# Bipolar_Offset_Shifter.net
KiCad netlist of a schematic drawn in Altium Designer
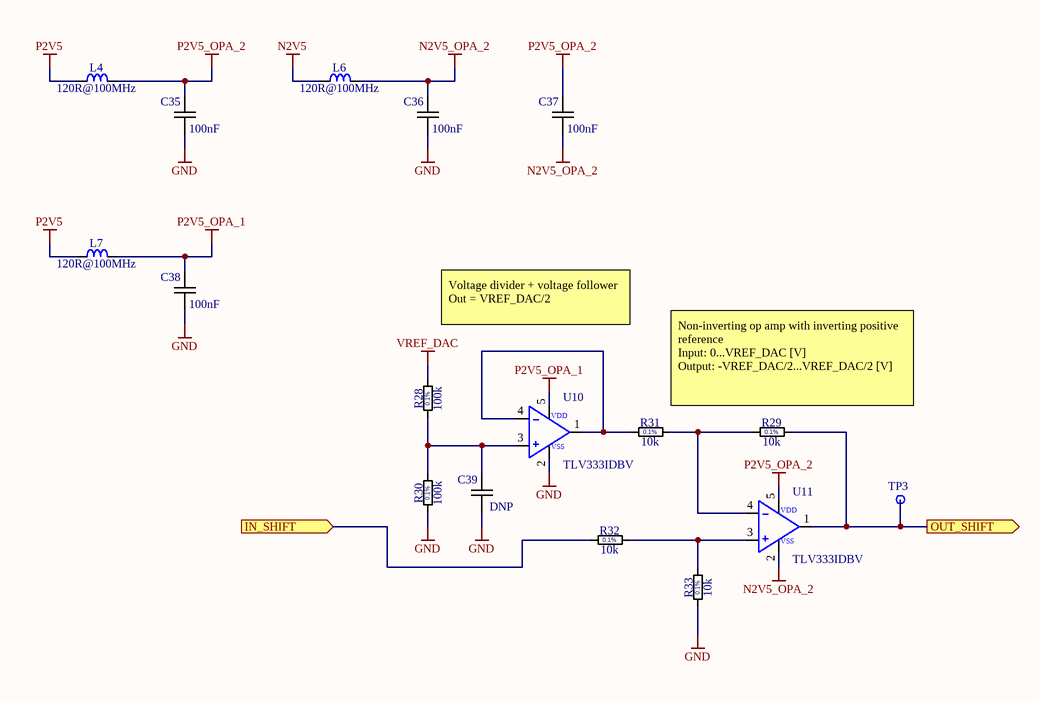
[diagram p0: Bipolar_Offset_Shifter.SchDoc]

(export (version "E")
  (design (tool "Eeschema 10.0.6"))
  (components
    (comp (ref "C35")
      (value "100nF")
      (footprint "CAPC0603X90N")
      (description "Non-polarised capacitor")
      (fields (field (name "MANUFACTURER PART NUMBER") "VJ0603Y104KXJCW1BC"))
      (libsource (lib "Capacitors") (part "Capacitor - non polarized"))
    )
    (comp (ref "C36")
      (value "100nF")
      (footprint "CAPC0603X90N")
      (description "Non-polarised capacitor")
      (fields (field (name "MANUFACTURER PART NUMBER") "VJ0603Y104KXJCW1BC"))
      (libsource (lib "Capacitors") (part "Capacitor - non polarized"))
    )
    (comp (ref "C37")
      (value "100nF")
      (footprint "CAPC0603X90N")
      (description "Non-polarised capacitor")
      (fields (field (name "MANUFACTURER PART NUMBER") "VJ0603Y104KXJCW1BC"))
      (libsource (lib "Capacitors") (part "Capacitor - non polarized"))
    )
    (comp (ref "C38")
      (value "100nF")
      (footprint "CAPC0603X90N")
      (description "Non-polarised capacitor")
      (fields (field (name "MANUFACTURER PART NUMBER") "VJ0603Y104KXJCW1BC"))
      (libsource (lib "Capacitors") (part "Capacitor - non polarized"))
    )
    (comp (ref "C39")
      (value "DNP")
      (footprint "CAPC0603X90N")
      (description "Non-polarised capacitor")
      (fields (field (name "MANUFACTURER PART NUMBER") "UNDEFINED"))
      (libsource (lib "Capacitors") (part "Capacitor - non polarized"))
    )
    (comp (ref "L4")
      (value "120R@100MHz")
      (footprint "INDC0603X90N")
      (description "Ferrite Bead")
      (fields (field (name "MANUFACTURER PART NUMBER") "BLM18PG121SN1D") (field (name "TOLERANCE") "25%"))
      (libsource (lib "Inductors") (part "Inductor"))
    )
    (comp (ref "L6")
      (value "120R@100MHz")
      (footprint "INDC0603X90N")
      (description "Ferrite Bead")
      (fields (field (name "MANUFACTURER PART NUMBER") "BLM18PG121SN1D") (field (name "TOLERANCE") "25%"))
      (libsource (lib "Inductors") (part "Inductor"))
    )
    (comp (ref "L7")
      (value "120R@100MHz")
      (footprint "INDC0603X90N")
      (description "Ferrite Bead")
      (fields (field (name "MANUFACTURER PART NUMBER") "BLM18PG121SN1D") (field (name "TOLERANCE") "25%"))
      (libsource (lib "Inductors") (part "Inductor"))
    )
    (comp (ref "R28")
      (value "100k")
      (footprint "RESC0603X60N")
      (description "General Purpose Thick Film Chip Resistor")
      (fields (field (name "MANUFACTURER PART NUMBER") "RT0603BRD07100KL") (field (name "TOLERANCE") "0.10%"))
      (libsource (lib "Resistors") (part "Resistor - 0.1%"))
    )
    (comp (ref "R29")
      (value "10k")
      (footprint "RESC0603X60N")
      (description "General Purpose Thick Film Chip Resistor")
      (fields (field (name "MANUFACTURER PART NUMBER") "RT0603BRD0710KL") (field (name "TOLERANCE") "0.10%"))
      (libsource (lib "Resistors") (part "Resistor - 0.1%"))
    )
    (comp (ref "R30")
      (value "100k")
      (footprint "RESC0603X60N")
      (description "General Purpose Thick Film Chip Resistor")
      (fields (field (name "MANUFACTURER PART NUMBER") "RT0603BRD07100KL") (field (name "TOLERANCE") "0.10%"))
      (libsource (lib "Resistors") (part "Resistor - 0.1%"))
    )
    (comp (ref "R31")
      (value "10k")
      (footprint "RESC0603X60N")
      (description "General Purpose Thick Film Chip Resistor")
      (fields (field (name "MANUFACTURER PART NUMBER") "RT0603BRD0710KL") (field (name "TOLERANCE") "0.10%"))
      (libsource (lib "Resistors") (part "Resistor - 0.1%"))
    )
    (comp (ref "R32")
      (value "10k")
      (footprint "RESC0603X60N")
      (description "General Purpose Thick Film Chip Resistor")
      (fields (field (name "MANUFACTURER PART NUMBER") "RT0603BRD0710KL") (field (name "TOLERANCE") "0.10%"))
      (libsource (lib "Resistors") (part "Resistor - 0.1%"))
    )
    (comp (ref "R33")
      (value "10k")
      (footprint "RESC0603X60N")
      (description "General Purpose Thick Film Chip Resistor")
      (fields (field (name "MANUFACTURER PART NUMBER") "RT0603BRD0710KL") (field (name "TOLERANCE") "0.10%"))
      (libsource (lib "Resistors") (part "Resistor - 0.1%"))
    )
    (comp (ref "TP3")
      (value "TestPoint")
      (footprint "TESTPOINT_SMD_C1P27MM")
      (description "1.27mm diameter SMD Test Point Area")
      (libsource (lib "Mechanical_and_PCB_Features") (part "Test Point"))
    )
    (comp (ref "U10")
      (value "TLV333IDBV")
      (footprint "SOT23-5")
      (libsource (lib "ICs_and_Semiconductors") (part "TLV333IDBV"))
    )
    (comp (ref "U11")
      (value "TLV333IDBV")
      (footprint "SOT23-5")
      (libsource (lib "ICs_and_Semiconductors") (part "TLV333IDBV"))
    )
  )
  (nets
    (net (code "1") (name "/IN_SHIFT") (class "Default")
      (node (ref "R32") (pin "1") (pinfunction "1_1") (pintype "passive"))
    )
    (net (code "2") (name "/OUT_SHIFT") (class "Default")
      (node (ref "R29") (pin "2") (pinfunction "2_2") (pintype "passive"))
      (node (ref "TP3") (pin "1") (pinfunction "1_1") (pintype "bidirectional"))
      (node (ref "U11") (pin "1") (pinfunction "1_1") (pintype "passive"))
    )
    (net (code "3") (name "GND") (class "Default")
      (node (ref "C35") (pin "2") (pinfunction "2_2") (pintype "passive"))
      (node (ref "C36") (pin "2") (pinfunction "2_2") (pintype "passive"))
      (node (ref "C38") (pin "2") (pinfunction "2_2") (pintype "passive"))
      (node (ref "C39") (pin "2") (pinfunction "2_2") (pintype "passive"))
      (node (ref "R30") (pin "1") (pinfunction "1_1") (pintype "passive"))
      (node (ref "R33") (pin "1") (pinfunction "1_1") (pintype "passive"))
      (node (ref "U10") (pin "2") (pinfunction "VSS_2") (pintype "power_in"))
    )
    (net (code "4") (name "N2V5") (class "Default")
      (node (ref "L6") (pin "1") (pinfunction "1_1") (pintype "passive"))
    )
    (net (code "5") (name "N2V5_OPA_2") (class "Default")
      (node (ref "C36") (pin "1") (pinfunction "1_1") (pintype "passive"))
      (node (ref "C37") (pin "2") (pinfunction "2_2") (pintype "passive"))
      (node (ref "L6") (pin "2") (pinfunction "2_2") (pintype "passive"))
      (node (ref "U11") (pin "2") (pinfunction "VSS_2") (pintype "power_in"))
    )
    (net (code "6") (name "Net-(C39-Pad1)") (class "Default")
      (node (ref "C39") (pin "1") (pinfunction "1_1") (pintype "passive"))
      (node (ref "R28") (pin "1") (pinfunction "1_1") (pintype "passive"))
      (node (ref "R30") (pin "2") (pinfunction "2_2") (pintype "passive"))
      (node (ref "U10") (pin "3") (pinfunction "3_3") (pintype "passive"))
    )
    (net (code "7") (name "Net-(R29-Pad1)") (class "Default")
      (node (ref "R29") (pin "1") (pinfunction "1_1") (pintype "passive"))
      (node (ref "R31") (pin "2") (pinfunction "2_2") (pintype "passive"))
      (node (ref "U11") (pin "4") (pinfunction "4_4") (pintype "passive"))
    )
    (net (code "8") (name "Net-(R31-Pad1)") (class "Default")
      (node (ref "R31") (pin "1") (pinfunction "1_1") (pintype "passive"))
      (node (ref "U10") (pin "1") (pinfunction "1_1") (pintype "passive"))
      (node (ref "U10") (pin "4") (pinfunction "4_4") (pintype "passive"))
    )
    (net (code "9") (name "Net-(R32-Pad2)") (class "Default")
      (node (ref "R32") (pin "2") (pinfunction "2_2") (pintype "passive"))
      (node (ref "R33") (pin "2") (pinfunction "2_2") (pintype "passive"))
      (node (ref "U11") (pin "3") (pinfunction "3_3") (pintype "passive"))
    )
    (net (code "10") (name "P2V5") (class "Default")
      (node (ref "L4") (pin "1") (pinfunction "1_1") (pintype "passive"))
      (node (ref "L7") (pin "1") (pinfunction "1_1") (pintype "passive"))
    )
    (net (code "11") (name "P2V5_OPA_1") (class "Default")
      (node (ref "C38") (pin "1") (pinfunction "1_1") (pintype "passive"))
      (node (ref "L7") (pin "2") (pinfunction "2_2") (pintype "passive"))
      (node (ref "U10") (pin "5") (pinfunction "VDD_5") (pintype "power_in"))
    )
    (net (code "12") (name "P2V5_OPA_2") (class "Default")
      (node (ref "C35") (pin "1") (pinfunction "1_1") (pintype "passive"))
      (node (ref "C37") (pin "1") (pinfunction "1_1") (pintype "passive"))
      (node (ref "L4") (pin "2") (pinfunction "2_2") (pintype "passive"))
      (node (ref "U11") (pin "5") (pinfunction "VDD_5") (pintype "power_in"))
    )
    (net (code "13") (name "VREF_DAC") (class "Default")
      (node (ref "R28") (pin "2") (pinfunction "2_2") (pintype "passive"))
    )
  )
)
